# ESP-01F.net
KiCad netlist of a schematic drawn in Altium Designer
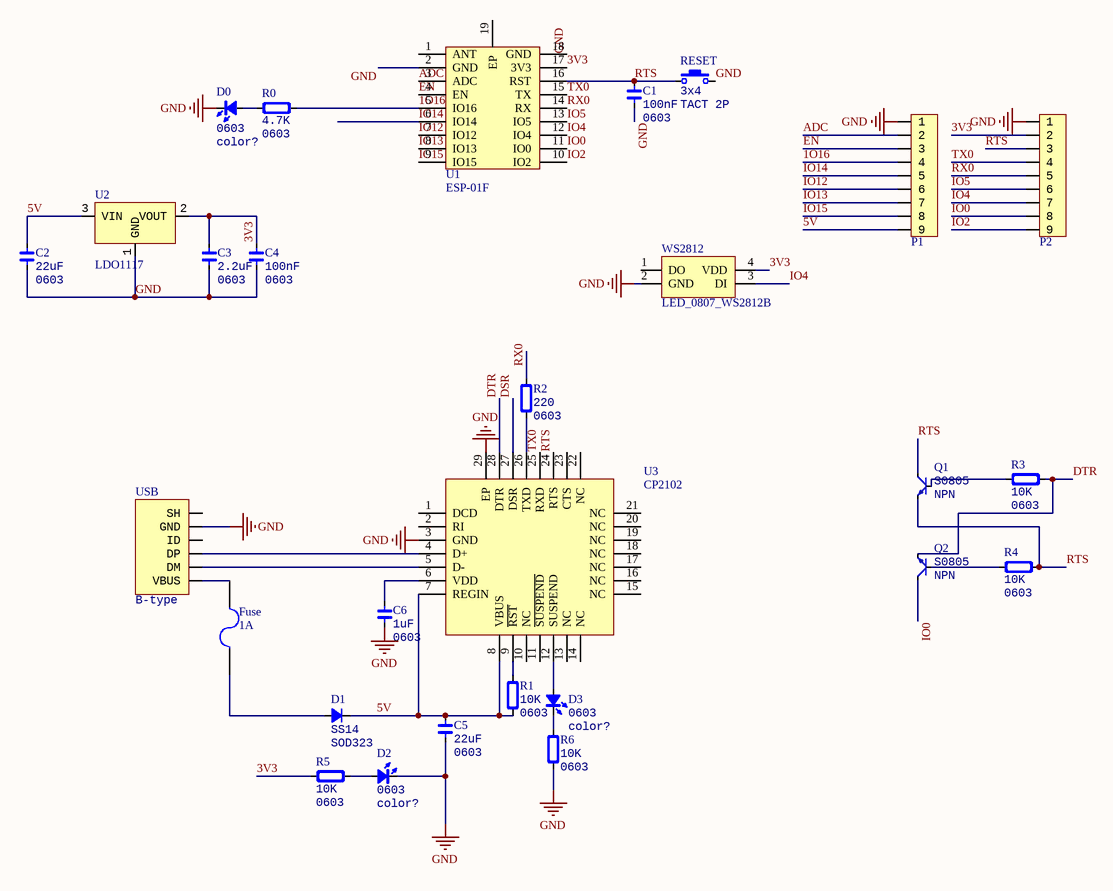
[diagram p0: ESP-01F.SchDoc]

(export (version "E")
  (design (tool "Eeschema 10.0.6"))
  (components
    (comp (ref "C1")
      (value "100nF")
      (footprint "CAP_0603")
      (description "Capacitor")
      (fields (field (name "TYPE") "0603") (field (name "Comment") "C0603"))
      (libsource (lib "Integrated_Library") (part "Cap_0603"))
    )
    (comp (ref "C2")
      (value "22uF")
      (footprint "CAP_0603")
      (description "Capacitor")
      (fields (field (name "TYPE") "0603") (field (name "Comment") "C0603"))
      (libsource (lib "Integrated_Library") (part "Cap_0603"))
    )
    (comp (ref "C3")
      (value "2.2uF")
      (footprint "CAP_0603")
      (description "Capacitor")
      (fields (field (name "TYPE") "0603") (field (name "Comment") "C0603"))
      (libsource (lib "Integrated_Library") (part "Cap_0603"))
    )
    (comp (ref "C4")
      (value "100nF")
      (footprint "CAP_0603")
      (description "Capacitor")
      (fields (field (name "TYPE") "0603") (field (name "Comment") "C0603"))
      (libsource (lib "Integrated_Library") (part "Cap_0603"))
    )
    (comp (ref "C5")
      (value "22uF")
      (footprint "CAP_0603")
      (description "Capacitor")
      (fields (field (name "TYPE") "0603") (field (name "Comment") "C0603"))
      (libsource (lib "Integrated_Library") (part "Cap_0603"))
    )
    (comp (ref "C6")
      (value "1uF")
      (footprint "CAP_0603")
      (description "Capacitor")
      (fields (field (name "TYPE") "0603") (field (name "Comment") "C0603"))
      (libsource (lib "Integrated_Library") (part "Cap_0603"))
    )
    (comp (ref "D0")
      (value "color?")
      (footprint "LED_0603_RED")
      (description "LED")
      (fields (field (name "TYPE") "0603"))
      (libsource (lib "") (part "LED_0603_1"))
    )
    (comp (ref "D1")
      (value "SS14")
      (footprint "SOD-323")
      (description "Diode")
      (fields (field (name "TYPE") "SOD323"))
      (libsource (lib "Integrated_Library") (part "Diode_SOD323"))
    )
    (comp (ref "D2")
      (value "color?")
      (footprint "LED_0603_RED")
      (description "LED")
      (fields (field (name "TYPE") "0603"))
      (libsource (lib "Integrated_Library") (part "LED_0603"))
    )
    (comp (ref "D3")
      (value "color?")
      (footprint "LED_0603_RED")
      (description "LED")
      (fields (field (name "TYPE") "0603"))
      (libsource (lib "") (part "LED_0603_2"))
    )
    (comp (ref "Fuse")
      (value "1A")
      (footprint "1206")
      (description "保险丝")
      (fields (field (name "Comment") "Fuse") (field (name "PUBLISHER") "Altium Limited"))
      (libsource (lib "PPD") (part "Fuse 2"))
    )
    (comp (ref "P1")
      (value "HDR1x9.54")
      (footprint "HDR1X9_2.54_180")
      (description "Header")
      (libsource (lib "Integrated_Library") (part "HDR1x9_2.54"))
    )
    (comp (ref "P2")
      (value "HDR1x9.54")
      (footprint "HDR1X9_2.54_180")
      (description "Header")
      (libsource (lib "Integrated_Library") (part "HDR1x9_2.54"))
    )
    (comp (ref "Q1")
      (value "S0805")
      (footprint "SOT23-3")
      (description "Transistor")
      (fields (field (name "TYPE") "NPN"))
      (libsource (lib "Integrated_Library") (part "BJT_NPN"))
    )
    (comp (ref "Q2")
      (value "S0805")
      (footprint "SOT23-3")
      (description "Transistor")
      (fields (field (name "TYPE") "NPN"))
      (libsource (lib "Integrated_Library") (part "BJT_NPN"))
    )
    (comp (ref "R0")
      (value "4.7K")
      (footprint "RES_0603")
      (description "Resistor")
      (fields (field (name "TYPE") "0603") (field (name "Comment") "R0603"))
      (libsource (lib "Integrated_Library") (part "Res_0603"))
    )
    (comp (ref "R1")
      (value "10K")
      (footprint "RES_0603")
      (description "Resistor")
      (fields (field (name "TYPE") "0603") (field (name "Comment") "R0603"))
      (libsource (lib "Integrated_Library") (part "Res_0603"))
    )
    (comp (ref "R2")
      (value "220")
      (footprint "RES_0603")
      (description "Resistor")
      (fields (field (name "TYPE") "0603") (field (name "Comment") "R0603"))
      (libsource (lib "Integrated_Library") (part "Res_0603"))
    )
    (comp (ref "R3")
      (value "10K")
      (footprint "RES_0603")
      (description "Resistor")
      (fields (field (name "TYPE") "0603") (field (name "Comment") "R0603"))
      (libsource (lib "Integrated_Library") (part "Res_0603"))
    )
    (comp (ref "R4")
      (value "10K")
      (footprint "RES_0603")
      (description "Resistor")
      (fields (field (name "TYPE") "0603") (field (name "Comment") "R0603"))
      (libsource (lib "Integrated_Library") (part "Res_0603"))
    )
    (comp (ref "R5")
      (value "10K")
      (footprint "RES_0603")
      (description "Resistor")
      (fields (field (name "TYPE") "0603") (field (name "Comment") "R0603"))
      (libsource (lib "Integrated_Library") (part "Res_0603"))
    )
    (comp (ref "R6")
      (value "10K")
      (footprint "RES_0603")
      (description "Resistor")
      (fields (field (name "TYPE") "0603") (field (name "Comment") "R0603"))
      (libsource (lib "Integrated_Library") (part "Res_0603"))
    )
    (comp (ref "RESET")
      (value "3x4")
      (footprint "ButtonTACT_3x4x2_180")
      (description "Button")
      (fields (field (name "TYPE") "TACT 2P") (field (name "Comment") "TACT 2P"))
      (libsource (lib "Integrated_Library") (part "ButtonTACT_3x4x2_180"))
    )
    (comp (ref "U1") (value "ESP-01F") (footprint "ESP-01F") (libsource (lib "PPD") (part "ESP-01F")))
    (comp (ref "U2")
      (value "LDO1117")
      (footprint "SOT89-3")
      (description "Power")
      (libsource (lib "Integrated_Library") (part "LDO1117"))
    )
    (comp (ref "U3") (value "CP2102") (footprint "QFN28,5X5") (libsource (lib "PPD") (part "CP2102")))
    (comp (ref "USB")
      (value "MicroUSB")
      (footprint "USB_Micro-AB")
      (description "USB")
      (fields (field (name "TYPE") "B-type"))
      (libsource (lib "Integrated_Library") (part "USB_Micro"))
    )
    (comp (ref "WS2812")
      (value "LED_0807_WS2812B")
      (footprint "WS28112_0807")
      (libsource (lib "PPD") (part "LED_0807_WS2812B"))
    )
  )
  (nets
    (net (code "1") (name "/1O16") (class "Default")
      (node (ref "P1") (pin "4") (pinfunction "4_4") (pintype "passive"))
      (node (ref "R0") (pin "1") (pinfunction "1_1") (pintype "passive"))
      (node (ref "U1") (pin "5") (pinfunction "IO16_5") (pintype "passive"))
    )
    (net (code "2") (name "/3V3") (class "Default")
      (node (ref "C3") (pin "2") (pinfunction "2_2") (pintype "passive"))
      (node (ref "C4") (pin "2") (pinfunction "2_2") (pintype "passive"))
      (node (ref "P2") (pin "2") (pinfunction "2_2") (pintype "passive"))
      (node (ref "R5") (pin "2") (pinfunction "2_2") (pintype "passive"))
      (node (ref "U1") (pin "17") (pinfunction "3V3_17") (pintype "passive"))
      (node (ref "U2") (pin "2") (pinfunction "VOUT_2") (pintype "passive"))
      (node (ref "WS2812") (pin "4") (pinfunction "VDD_4") (pintype "passive"))
    )
    (net (code "3") (name "/5V") (class "Default")
      (node (ref "C2") (pin "2") (pinfunction "2_2") (pintype "passive"))
      (node (ref "C5") (pin "2") (pinfunction "2_2") (pintype "passive"))
      (node (ref "D1") (pin "2") (pinfunction "K_2") (pintype "passive"))
      (node (ref "P1") (pin "9") (pinfunction "9_9") (pintype "passive"))
      (node (ref "R1") (pin "1") (pinfunction "1_1") (pintype "passive"))
      (node (ref "U2") (pin "3") (pinfunction "VIN_3") (pintype "passive"))
      (node (ref "U3") (pin "7") (pinfunction "REGIN_7") (pintype "passive"))
      (node (ref "U3") (pin "8") (pinfunction "VBUS_8") (pintype "passive"))
    )
    (net (code "4") (name "/ADC") (class "Default")
      (node (ref "P1") (pin "2") (pinfunction "2_2") (pintype "passive"))
      (node (ref "U1") (pin "3") (pinfunction "ADC_3") (pintype "passive"))
    )
    (net (code "5") (name "/DSR") (class "Default")
      (node (ref "U3") (pin "27") (pinfunction "DSR_27") (pintype "passive"))
    )
    (net (code "6") (name "/DTR") (class "Default")
      (node (ref "Q2") (pin "2") (pinfunction "E_2") (pintype "passive"))
      (node (ref "R3") (pin "1") (pinfunction "1_1") (pintype "passive"))
      (node (ref "U3") (pin "28") (pinfunction "DTR_28") (pintype "passive"))
    )
    (net (code "7") (name "/EN") (class "Default")
      (node (ref "P1") (pin "3") (pinfunction "3_3") (pintype "passive"))
      (node (ref "U1") (pin "4") (pinfunction "EN_4") (pintype "passive"))
    )
    (net (code "8") (name "/IO0") (class "Default")
      (node (ref "P2") (pin "8") (pinfunction "8_8") (pintype "passive"))
      (node (ref "Q2") (pin "3") (pinfunction "C_3") (pintype "passive"))
      (node (ref "U1") (pin "11") (pinfunction "IO0_11") (pintype "passive"))
    )
    (net (code "9") (name "/IO2") (class "Default")
      (node (ref "P2") (pin "9") (pinfunction "9_9") (pintype "passive"))
      (node (ref "U1") (pin "10") (pinfunction "IO2_10") (pintype "passive"))
    )
    (net (code "10") (name "/IO4") (class "Default")
      (node (ref "P2") (pin "7") (pinfunction "7_7") (pintype "passive"))
      (node (ref "U1") (pin "12") (pinfunction "IO4_12") (pintype "passive"))
      (node (ref "WS2812") (pin "3") (pinfunction "DI_3") (pintype "passive"))
    )
    (net (code "11") (name "/IO5") (class "Default")
      (node (ref "P2") (pin "6") (pinfunction "6_6") (pintype "passive"))
      (node (ref "U1") (pin "13") (pinfunction "IO5_13") (pintype "passive"))
    )
    (net (code "12") (name "/IO12") (class "Default")
      (node (ref "P1") (pin "6") (pinfunction "6_6") (pintype "passive"))
      (node (ref "U1") (pin "7") (pinfunction "IO12_7") (pintype "passive"))
    )
    (net (code "13") (name "/IO13") (class "Default")
      (node (ref "P1") (pin "7") (pinfunction "7_7") (pintype "passive"))
      (node (ref "U1") (pin "8") (pinfunction "IO13_8") (pintype "passive"))
    )
    (net (code "14") (name "/IO14") (class "Default")
      (node (ref "P1") (pin "5") (pinfunction "5_5") (pintype "passive"))
      (node (ref "U1") (pin "6") (pinfunction "IO14_6") (pintype "passive"))
    )
    (net (code "15") (name "/IO15") (class "Default")
      (node (ref "P1") (pin "8") (pinfunction "8_8") (pintype "passive"))
      (node (ref "U1") (pin "9") (pinfunction "IO15_9") (pintype "passive"))
    )
    (net (code "16") (name "/RTS") (class "Default")
      (node (ref "C1") (pin "2") (pinfunction "2_2") (pintype "passive"))
      (node (ref "P2") (pin "3") (pinfunction "3_3") (pintype "passive"))
      (node (ref "Q1") (pin "2") (pinfunction "E_2") (pintype "passive"))
      (node (ref "Q1") (pin "3") (pinfunction "C_3") (pintype "passive"))
      (node (ref "R4") (pin "1") (pinfunction "1_1") (pintype "passive"))
      (node (ref "RESET") (pin "1") (pinfunction "1_1") (pintype "passive"))
      (node (ref "U1") (pin "16") (pinfunction "RST_16") (pintype "passive"))
      (node (ref "U3") (pin "24") (pinfunction "RTS_24") (pintype "passive"))
    )
    (net (code "17") (name "/RX0") (class "Default")
      (node (ref "P2") (pin "5") (pinfunction "5_5") (pintype "passive"))
      (node (ref "R2") (pin "2") (pinfunction "2_2") (pintype "passive"))
      (node (ref "U1") (pin "14") (pinfunction "RX_14") (pintype "passive"))
    )
    (net (code "18") (name "/TX0") (class "Default")
      (node (ref "P2") (pin "4") (pinfunction "4_4") (pintype "passive"))
      (node (ref "U1") (pin "15") (pinfunction "TX_15") (pintype "passive"))
      (node (ref "U3") (pin "25") (pinfunction "RXD_25") (pintype "passive"))
    )
    (net (code "19") (name "GND") (class "Default")
      (node (ref "C1") (pin "1") (pinfunction "1_1") (pintype "passive"))
      (node (ref "C2") (pin "1") (pinfunction "1_1") (pintype "passive"))
      (node (ref "C3") (pin "1") (pinfunction "1_1") (pintype "passive"))
      (node (ref "C4") (pin "1") (pinfunction "1_1") (pintype "passive"))
      (node (ref "C5") (pin "1") (pinfunction "1_1") (pintype "passive"))
      (node (ref "C6") (pin "1") (pinfunction "1_1") (pintype "passive"))
      (node (ref "D0") (pin "2") (pinfunction "K_2") (pintype "passive"))
      (node (ref "D2") (pin "2") (pinfunction "K_2") (pintype "passive"))
      (node (ref "P1") (pin "1") (pinfunction "1_1") (pintype "passive"))
      (node (ref "P2") (pin "1") (pinfunction "1_1") (pintype "passive"))
      (node (ref "R6") (pin "1") (pinfunction "1_1") (pintype "passive"))
      (node (ref "RESET") (pin "2") (pinfunction "2_2") (pintype "passive"))
      (node (ref "U1") (pin "18") (pinfunction "GND_18") (pintype "passive"))
      (node (ref "U1") (pin "2") (pinfunction "GND_2") (pintype "passive"))
      (node (ref "U2") (pin "1") (pinfunction "GND_1") (pintype "passive"))
      (node (ref "U3") (pin "29") (pinfunction "EP_29") (pintype "passive"))
      (node (ref "U3") (pin "3") (pinfunction "GND_3") (pintype "passive"))
      (node (ref "USB") (pin "5") (pinfunction "GND_5") (pintype "passive"))
      (node (ref "WS2812") (pin "2") (pinfunction "GND_2") (pintype "passive"))
    )
    (net (code "20") (name "Net-(D0-A)") (class "Default")
      (node (ref "D0") (pin "1") (pinfunction "A_1") (pintype "passive"))
      (node (ref "R0") (pin "2") (pinfunction "2_2") (pintype "passive"))
    )
    (net (code "21") (name "Net-(D1-A)") (class "Default")
      (node (ref "D1") (pin "1") (pinfunction "A_1") (pintype "passive"))
      (node (ref "Fuse") (pin "1") (pinfunction "1_1") (pintype "passive"))
    )
    (net (code "22") (name "Net-(D2-A)") (class "Default")
      (node (ref "D2") (pin "1") (pinfunction "A_1") (pintype "passive"))
      (node (ref "R5") (pin "1") (pinfunction "1_1") (pintype "passive"))
    )
    (net (code "23") (name "Net-(D3-A)") (class "Default")
      (node (ref "D3") (pin "1") (pinfunction "A_1") (pintype "passive"))
      (node (ref "U3") (pin "12") (pinfunction "SUSPEND_12") (pintype "passive"))
    )
    (net (code "24") (name "Net-(D3-K)") (class "Default")
      (node (ref "D3") (pin "2") (pinfunction "K_2") (pintype "passive"))
      (node (ref "R6") (pin "2") (pinfunction "2_2") (pintype "passive"))
    )
    (net (code "25") (name "Net-(Q1-B)") (class "Default")
      (node (ref "Q1") (pin "1") (pinfunction "B_1") (pintype "passive"))
      (node (ref "R3") (pin "2") (pinfunction "2_2") (pintype "passive"))
    )
    (net (code "26") (name "Net-(Q2-B)") (class "Default")
      (node (ref "Q2") (pin "1") (pinfunction "B_1") (pintype "passive"))
      (node (ref "R4") (pin "2") (pinfunction "2_2") (pintype "passive"))
    )
    (net (code "27") (name "Net-(U3-D+)") (class "Default")
      (node (ref "U3") (pin "4") (pinfunction "D+_4") (pintype "passive"))
      (node (ref "USB") (pin "3") (pinfunction "DP_3") (pintype "passive"))
    )
    (net (code "28") (name "Net-(U3-D-)") (class "Default")
      (node (ref "U3") (pin "5") (pinfunction "D-_5") (pintype "passive"))
      (node (ref "USB") (pin "2") (pinfunction "DM_2") (pintype "passive"))
    )
    (net (code "29") (name "Net-(U3-TXD)") (class "Default")
      (node (ref "R2") (pin "1") (pinfunction "1_1") (pintype "passive"))
      (node (ref "U3") (pin "26") (pinfunction "TXD_26") (pintype "passive"))
    )
    (net (code "30") (name "Net-(U3-VDD)") (class "Default")
      (node (ref "C6") (pin "2") (pinfunction "2_2") (pintype "passive"))
      (node (ref "U3") (pin "6") (pinfunction "VDD_6") (pintype "passive"))
    )
    (net (code "31") (name "Net-(U3-~{RST})") (class "Default")
      (node (ref "R1") (pin "2") (pinfunction "2_2") (pintype "passive"))
      (node (ref "U3") (pin "9") (pinfunction "~{RST}_9") (pintype "passive"))
    )
    (net (code "32") (name "Net-(USB-VBUS)") (class "Default")
      (node (ref "Fuse") (pin "2") (pinfunction "2_2") (pintype "passive"))
      (node (ref "USB") (pin "1") (pinfunction "VBUS_1") (pintype "passive"))
    )
    (net (code "33") (name "unconnected-(U1-ANT-Pad1)") (class "Default")
      (node (ref "U1") (pin "1") (pinfunction "ANT_1") (pintype "passive"))
    )
    (net (code "34") (name "unconnected-(U1-EP-Pad19)") (class "Default")
      (node (ref "U1") (pin "19") (pinfunction "EP_19") (pintype "passive"))
    )
    (net (code "35") (name "unconnected-(U3-CTS-Pad23)") (class "Default")
      (node (ref "U3") (pin "23") (pinfunction "CTS_23") (pintype "passive"))
    )
    (net (code "36") (name "unconnected-(U3-DCD-Pad1)") (class "Default")
      (node (ref "U3") (pin "1") (pinfunction "DCD_1") (pintype "passive"))
    )
    (net (code "37") (name "unconnected-(U3-NC-Pad10)") (class "Default")
      (node (ref "U3") (pin "10") (pinfunction "NC_10") (pintype "passive"))
    )
    (net (code "38") (name "unconnected-(U3-NC-Pad13)") (class "Default")
      (node (ref "U3") (pin "13") (pinfunction "NC_13") (pintype "passive"))
    )
    (net (code "39") (name "unconnected-(U3-NC-Pad14)") (class "Default")
      (node (ref "U3") (pin "14") (pinfunction "NC_14") (pintype "passive"))
    )
    (net (code "40") (name "unconnected-(U3-NC-Pad15)") (class "Default")
      (node (ref "U3") (pin "15") (pinfunction "NC_15") (pintype "passive"))
    )
    (net (code "41") (name "unconnected-(U3-NC-Pad16)") (class "Default")
      (node (ref "U3") (pin "16") (pinfunction "NC_16") (pintype "passive"))
    )
    (net (code "42") (name "unconnected-(U3-NC-Pad17)") (class "Default")
      (node (ref "U3") (pin "17") (pinfunction "NC_17") (pintype "passive"))
    )
    (net (code "43") (name "unconnected-(U3-NC-Pad18)") (class "Default")
      (node (ref "U3") (pin "18") (pinfunction "NC_18") (pintype "passive"))
    )
    (net (code "44") (name "unconnected-(U3-NC-Pad19)") (class "Default")
      (node (ref "U3") (pin "19") (pinfunction "NC_19") (pintype "passive"))
    )
    (net (code "45") (name "unconnected-(U3-NC-Pad20)") (class "Default")
      (node (ref "U3") (pin "20") (pinfunction "NC_20") (pintype "passive"))
    )
    (net (code "46") (name "unconnected-(U3-NC-Pad21)") (class "Default")
      (node (ref "U3") (pin "21") (pinfunction "NC_21") (pintype "passive"))
    )
    (net (code "47") (name "unconnected-(U3-NC-Pad22)") (class "Default")
      (node (ref "U3") (pin "22") (pinfunction "NC_22") (pintype "passive"))
    )
    (net (code "48") (name "unconnected-(U3-RI-Pad2)") (class "Default")
      (node (ref "U3") (pin "2") (pinfunction "RI_2") (pintype "passive"))
    )
    (net (code "49") (name "unconnected-(U3-~{SUSPEND}-Pad11)") (class "Default")
      (node (ref "U3") (pin "11") (pinfunction "~{SUSPEND}_11") (pintype "passive"))
    )
    (net (code "50") (name "unconnected-(USB-ID-Pad4)") (class "Default")
      (node (ref "USB") (pin "4") (pinfunction "ID_4") (pintype "passive"))
    )
    (net (code "51") (name "unconnected-(USB-SH-Pad0)") (class "Default")
      (node (ref "USB") (pin "0") (pinfunction "SH_0") (pintype "passive"))
    )
    (net (code "52") (name "unconnected-(WS2812-DO-Pad1)") (class "Default")
      (node (ref "WS2812") (pin "1") (pinfunction "DO_1") (pintype "passive"))
    )
  )
)
